# SmartLURE.net
KiCad netlist of a schematic drawn in EAGLE
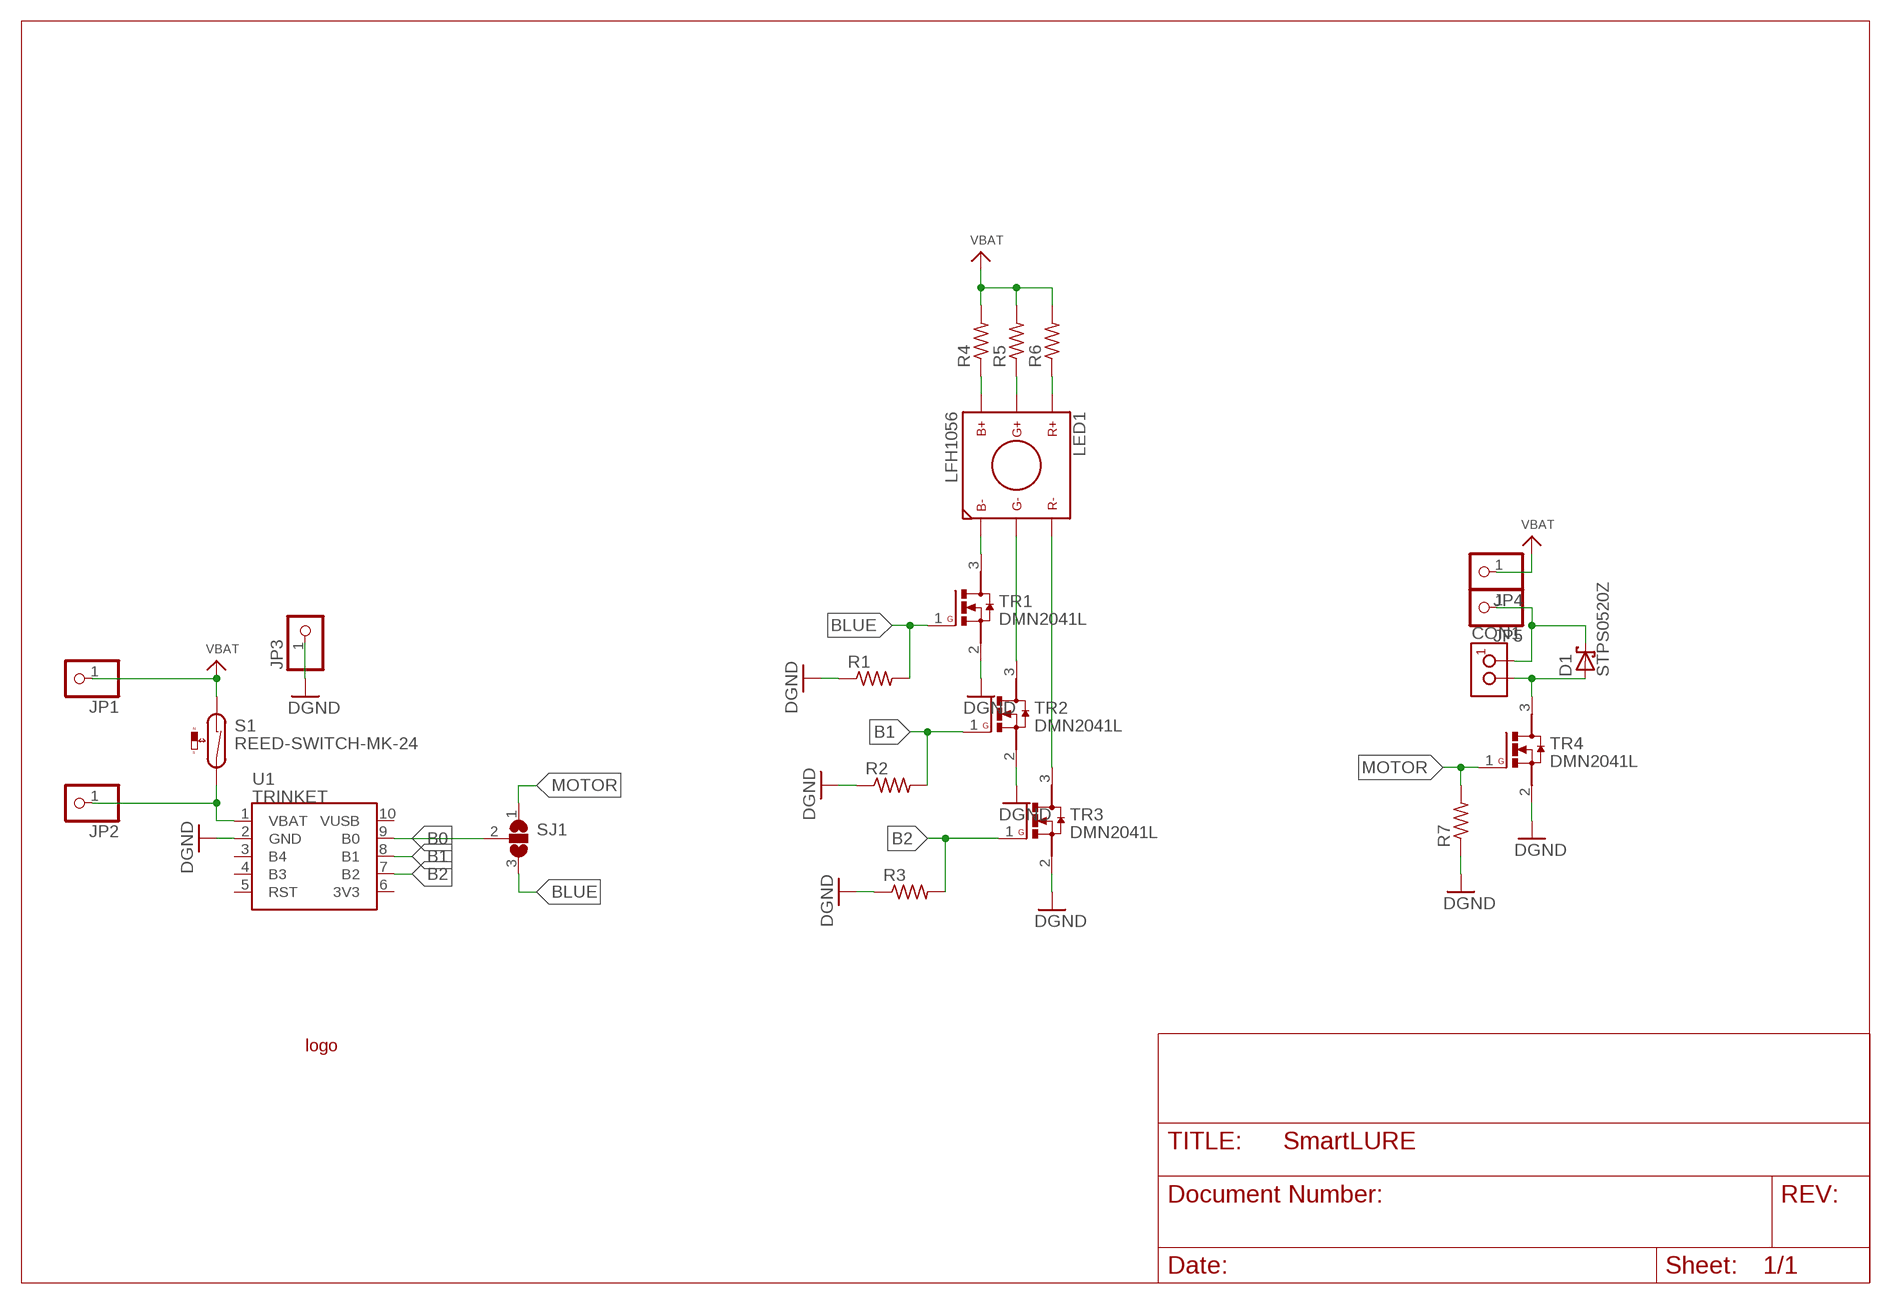
[diagram p0: schematic, sheet 1]

(export (version "E")
  (design (tool "Eeschema 10.0.6"))
  (components
    (comp (ref "CON1")
      (value "PINHEADER_1.27")
      (footprint "eagle-import:PINHEADER_1.27")
      (libsource (lib "eagle-import") (part "PINHEADER_1.27"))
    )
    (comp (ref "D1")
      (value "STPS0520Z")
      (footprint "eagle-import:SOD-123")
      (libsource (lib "eagle-import") (part "STPS0520Z"))
    )
    (comp (ref "JP1")
      (value "PINHD-1X1CB")
      (footprint "eagle-import:1X01-CLEANBIG")
      (libsource (lib "eagle-import") (part "PINHD-1X1CB"))
    )
    (comp (ref "JP2")
      (value "PINHD-1X1CB")
      (footprint "eagle-import:1X01-CLEANBIG")
      (libsource (lib "eagle-import") (part "PINHD-1X1CB"))
    )
    (comp (ref "JP3")
      (value "PINHD-1X1CB")
      (footprint "eagle-import:1X01-CLEANBIG")
      (libsource (lib "eagle-import") (part "PINHD-1X1CB"))
    )
    (comp (ref "JP4")
      (value "PINHD-1X1CB")
      (footprint "eagle-import:1X01-CLEANBIG")
      (libsource (lib "eagle-import") (part "PINHD-1X1CB"))
    )
    (comp (ref "JP5")
      (value "PINHD-1X1CB")
      (footprint "eagle-import:1X01-CLEANBIG")
      (libsource (lib "eagle-import") (part "PINHD-1X1CB"))
    )
    (comp (ref "LED1")
      (value "LFH1056")
      (footprint "eagle-import:LFH1056")
      (libsource (lib "eagle-import") (part "LFH1056"))
    )
    (comp (ref "LOGO1")
      (value "GRADEFREELOGO-10")
      (footprint "eagle-import:GRADEFREELOGO-10")
      (libsource (lib "eagle-import") (part "GRADEFREELOGO-10"))
    )
    (comp (ref "R1")
      (value "R0603(1608)")
      (footprint "eagle-import:R0603(1608)")
      (libsource (lib "eagle-import") (part "R0603(1608)"))
    )
    (comp (ref "R2")
      (value "R0603(1608)")
      (footprint "eagle-import:R0603(1608)")
      (libsource (lib "eagle-import") (part "R0603(1608)"))
    )
    (comp (ref "R3")
      (value "R0603(1608)")
      (footprint "eagle-import:R0603(1608)")
      (libsource (lib "eagle-import") (part "R0603(1608)"))
    )
    (comp (ref "R4")
      (value "R0603(1608)")
      (footprint "eagle-import:R0603(1608)")
      (libsource (lib "eagle-import") (part "R0603(1608)"))
    )
    (comp (ref "R5")
      (value "R0603(1608)")
      (footprint "eagle-import:R0603(1608)")
      (libsource (lib "eagle-import") (part "R0603(1608)"))
    )
    (comp (ref "R6")
      (value "R0603(1608)")
      (footprint "eagle-import:R0603(1608)")
      (libsource (lib "eagle-import") (part "R0603(1608)"))
    )
    (comp (ref "R7")
      (value "R0603(1608)")
      (footprint "eagle-import:R0603(1608)")
      (libsource (lib "eagle-import") (part "R0603(1608)"))
    )
    (comp (ref "S1")
      (value "REED-SWITCH-MK-24")
      (footprint "eagle-import:MK24")
      (libsource (lib "eagle-import") (part "REED-SWITCH-MK-24"))
    )
    (comp (ref "SJ1")
      (value "SJ2W")
      (footprint "eagle-import:SJ_2")
      (libsource (lib "eagle-import") (part "SJ2W"))
    )
    (comp (ref "TR1")
      (value "DMN2041L")
      (footprint "eagle-import:SOT23")
      (libsource (lib "eagle-import") (part "DMN2041L"))
    )
    (comp (ref "TR2")
      (value "DMN2041L")
      (footprint "eagle-import:SOT23")
      (libsource (lib "eagle-import") (part "DMN2041L"))
    )
    (comp (ref "TR3")
      (value "DMN2041L")
      (footprint "eagle-import:SOT23")
      (libsource (lib "eagle-import") (part "DMN2041L"))
    )
    (comp (ref "TR4")
      (value "DMN2041L")
      (footprint "eagle-import:SOT23")
      (libsource (lib "eagle-import") (part "DMN2041L"))
    )
    (comp (ref "U1")
      (value "TRINKET")
      (footprint "eagle-import:TRINKET")
      (libsource (lib "eagle-import") (part "TRINKET"))
    )
  )
  (nets
    (net (code "1") (name "B0") (class "Default")
      (node (ref "SJ1") (pin "2") (pinfunction "2_2") (pintype "passive"))
      (node (ref "U1") (pin "9") (pinfunction "B0_9") (pintype "bidirectional"))
    )
    (net (code "2") (name "B1") (class "Default")
      (node (ref "R2") (pin "2") (pinfunction "2_2") (pintype "passive"))
      (node (ref "TR2") (pin "1") (pinfunction "G_1") (pintype "bidirectional"))
      (node (ref "U1") (pin "8") (pinfunction "B1_8") (pintype "bidirectional"))
    )
    (net (code "3") (name "B2") (class "Default")
      (node (ref "R3") (pin "2") (pinfunction "2_2") (pintype "passive"))
      (node (ref "TR3") (pin "1") (pinfunction "G_1") (pintype "bidirectional"))
      (node (ref "U1") (pin "7") (pinfunction "B2_7") (pintype "bidirectional"))
    )
    (net (code "4") (name "BLUE") (class "Default")
      (node (ref "R1") (pin "2") (pinfunction "2_2") (pintype "passive"))
      (node (ref "SJ1") (pin "3") (pinfunction "3_3") (pintype "passive"))
      (node (ref "TR1") (pin "1") (pinfunction "G_1") (pintype "bidirectional"))
    )
    (net (code "5") (name "DGND") (class "Default")
      (node (ref "JP3") (pin "1") (pinfunction "1_1") (pintype "passive"))
      (node (ref "R1") (pin "1") (pinfunction "1_1") (pintype "passive"))
      (node (ref "R2") (pin "1") (pinfunction "1_1") (pintype "passive"))
      (node (ref "R3") (pin "1") (pinfunction "1_1") (pintype "passive"))
      (node (ref "R7") (pin "1") (pinfunction "1_1") (pintype "passive"))
      (node (ref "TR1") (pin "2") (pinfunction "S_2") (pintype "bidirectional"))
      (node (ref "TR2") (pin "2") (pinfunction "S_2") (pintype "bidirectional"))
      (node (ref "TR3") (pin "2") (pinfunction "S_2") (pintype "bidirectional"))
      (node (ref "TR4") (pin "2") (pinfunction "S_2") (pintype "bidirectional"))
      (node (ref "U1") (pin "2") (pinfunction "GND_2") (pintype "bidirectional"))
    )
    (net (code "6") (name "MOTOR") (class "Default")
      (node (ref "R7") (pin "2") (pinfunction "2_2") (pintype "passive"))
      (node (ref "SJ1") (pin "1") (pinfunction "1_1") (pintype "passive"))
      (node (ref "TR4") (pin "1") (pinfunction "G_1") (pintype "bidirectional"))
    )
    (net (code "7") (name "Net-(CON1-1)") (class "Default")
      (node (ref "CON1") (pin "P$1") (pinfunction "1_P$1") (pintype "passive"))
      (node (ref "D1") (pin "C") (pinfunction "C_C") (pintype "passive"))
      (node (ref "JP5") (pin "1") (pinfunction "1_1") (pintype "passive"))
    )
    (net (code "8") (name "Net-(CON1-2)") (class "Default")
      (node (ref "CON1") (pin "P$2") (pinfunction "2_P$2") (pintype "passive"))
      (node (ref "D1") (pin "A") (pinfunction "A_A") (pintype "passive"))
      (node (ref "TR4") (pin "3") (pinfunction "D_3") (pintype "bidirectional"))
    )
    (net (code "9") (name "Net-(LED1-PadB+)") (class "Default")
      (node (ref "LED1") (pin "B+") (pinfunction "B+_B+") (pintype "input"))
      (node (ref "R4") (pin "1") (pinfunction "1_1") (pintype "passive"))
    )
    (net (code "10") (name "Net-(LED1-PadG+)") (class "Default")
      (node (ref "LED1") (pin "G+") (pinfunction "G+_G+") (pintype "input"))
      (node (ref "R5") (pin "1") (pinfunction "1_1") (pintype "passive"))
    )
    (net (code "11") (name "Net-(LED1-PadR+)") (class "Default")
      (node (ref "LED1") (pin "R+") (pinfunction "R+_R+") (pintype "input"))
      (node (ref "R6") (pin "1") (pinfunction "1_1") (pintype "passive"))
    )
    (net (code "12") (name "Net-(TR1-D)") (class "Default")
      (node (ref "LED1") (pin "B-") (pinfunction "B-_B-") (pintype "input"))
      (node (ref "TR1") (pin "3") (pinfunction "D_3") (pintype "bidirectional"))
    )
    (net (code "13") (name "Net-(TR2-D)") (class "Default")
      (node (ref "LED1") (pin "G-") (pinfunction "G-_G-") (pintype "input"))
      (node (ref "TR2") (pin "3") (pinfunction "D_3") (pintype "bidirectional"))
    )
    (net (code "14") (name "Net-(TR3-D)") (class "Default")
      (node (ref "LED1") (pin "R-") (pinfunction "R-_R-") (pintype "input"))
      (node (ref "TR3") (pin "3") (pinfunction "D_3") (pintype "bidirectional"))
    )
    (net (code "15") (name "Net-(U1-VBAT)") (class "Default")
      (node (ref "JP2") (pin "1") (pinfunction "1_1") (pintype "passive"))
      (node (ref "S1") (pin "2") (pinfunction "2_2") (pintype "passive"))
      (node (ref "U1") (pin "1") (pinfunction "VBAT_1") (pintype "bidirectional"))
    )
    (net (code "16") (name "VBAT") (class "Default")
      (node (ref "JP1") (pin "1") (pinfunction "1_1") (pintype "passive"))
      (node (ref "JP4") (pin "1") (pinfunction "1_1") (pintype "passive"))
      (node (ref "R4") (pin "2") (pinfunction "2_2") (pintype "passive"))
      (node (ref "R5") (pin "2") (pinfunction "2_2") (pintype "passive"))
      (node (ref "R6") (pin "2") (pinfunction "2_2") (pintype "passive"))
      (node (ref "S1") (pin "1") (pinfunction "1_1") (pintype "passive"))
    )
    (net (code "17") (name "unconnected-(U1-3V3-Pad6)") (class "Default")
      (node (ref "U1") (pin "6") (pinfunction "3V3_6") (pintype "bidirectional"))
    )
    (net (code "18") (name "unconnected-(U1-B3-Pad4)") (class "Default")
      (node (ref "U1") (pin "4") (pinfunction "B3_4") (pintype "bidirectional"))
    )
    (net (code "19") (name "unconnected-(U1-B4-Pad3)") (class "Default")
      (node (ref "U1") (pin "3") (pinfunction "B4_3") (pintype "bidirectional"))
    )
    (net (code "20") (name "unconnected-(U1-RST-Pad5)") (class "Default")
      (node (ref "U1") (pin "5") (pinfunction "RST_5") (pintype "bidirectional"))
    )
    (net (code "21") (name "unconnected-(U1-VUSB-Pad10)") (class "Default")
      (node (ref "U1") (pin "10") (pinfunction "VUSB_10") (pintype "bidirectional"))
    )
  )
)
